# heater-control.net
KiCad netlist of a schematic drawn in Altium Designer
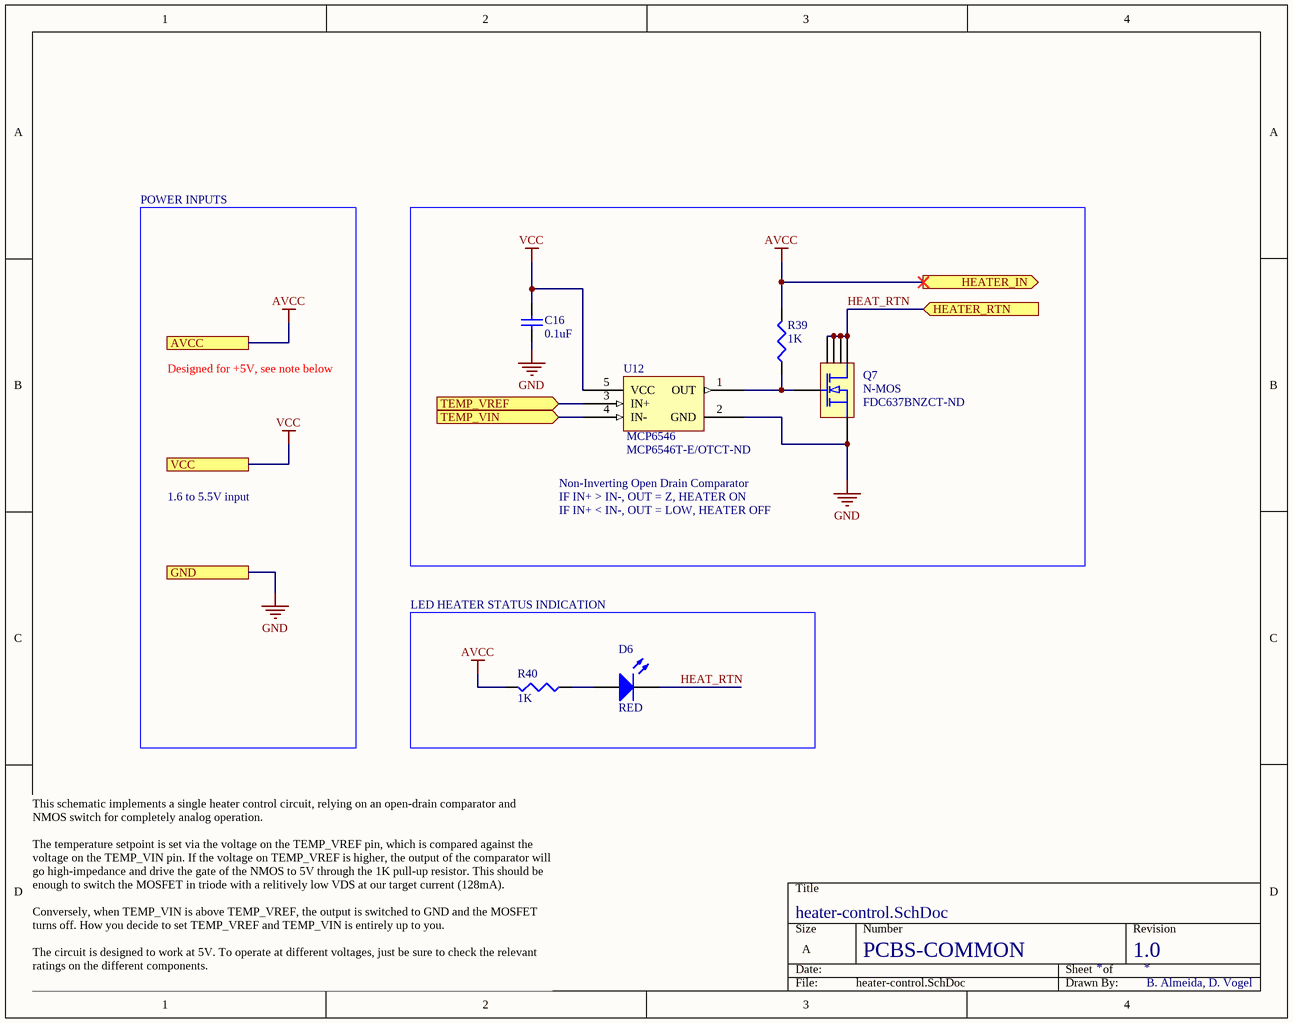
[diagram p0: heater-control.SchDoc]

(export (version "E")
  (design (tool "Eeschema 10.0.6"))
  (components
    (comp (ref "C16")
      (value "0.1uF")
      (footprint "1608[0603]")
      (description "Capacitor (Semiconductor SIM Model)")
      (fields (field (name "Comment") "100pF") (field (name "PUBLISHER") "Altium Limited"))
      (libsource (lib "Miscellaneous Devices") (part "Cap Semi"))
    )
    (comp (ref "D6")
      (value "RED")
      (footprint "0603-LED")
      (description "Typical RED, GREEN, YELLOW, AMBER GaAs LED")
      (fields (field (name "PUBLISHER") "Altium Limited"))
      (libsource (lib "Miscellaneous Devices") (part "LED2"))
    )
    (comp (ref "Q7")
      (value "N-MOS")
      (footprint "SOT95P280X145-6N")
      (description "N-MOS, low gate ON voltage")
      (fields (field (name "SUPPLIER PART NUMBER") "FDC637BNZCT-ND"))
      (libsource (lib "PAY") (part "FDC637BNZCT-ND"))
    )
    (comp (ref "R39")
      (value "1K")
      (footprint "J1-0603")
      (description "Resistor")
      (fields (field (name "PUBLISHER") "Altium Limited"))
      (libsource (lib "Miscellaneous Devices") (part "Res3"))
    )
    (comp (ref "R40")
      (value "1K")
      (footprint "J1-0603")
      (description "Resistor")
      (fields (field (name "PUBLISHER") "Altium Limited"))
      (libsource (lib "Miscellaneous Devices") (part "Res3"))
    )
    (comp (ref "U12")
      (value "MCP6546")
      (footprint "SOT-23-5_95P290X160-5N")
      (description "Open-drain output sub-microamp comparator.")
      (fields (field (name "SUPPLIER PART NUMBER 1") "MCP6546T-E/OTCT-ND"))
      (libsource (lib "PAY") (part "MCP6546"))
    )
  )
  (nets
    (net (code "1") (name "/HEAT_RTN") (class "Default")
      (node (ref "D6") (pin "2") (pinfunction "K_2") (pintype "passive"))
      (node (ref "Q7") (pin "1") (pinfunction "D_1") (pintype "passive"))
      (node (ref "Q7") (pin "2") (pinfunction "D_2") (pintype "passive"))
      (node (ref "Q7") (pin "5") (pinfunction "D_5") (pintype "passive"))
      (node (ref "Q7") (pin "6") (pinfunction "D_6") (pintype "passive"))
    )
    (net (code "2") (name "/TEMP_VIN") (class "Default")
      (node (ref "U12") (pin "4") (pinfunction "IN-_4") (pintype "input"))
    )
    (net (code "3") (name "/TEMP_VREF") (class "Default")
      (node (ref "U12") (pin "3") (pinfunction "IN+_3") (pintype "input"))
    )
    (net (code "4") (name "AVCC") (class "Default")
      (node (ref "R39") (pin "2") (pinfunction "2_2") (pintype "passive"))
      (node (ref "R40") (pin "2") (pinfunction "2_2") (pintype "passive"))
    )
    (net (code "5") (name "GND") (class "Default")
      (node (ref "C16") (pin "1") (pinfunction "1_1") (pintype "passive"))
      (node (ref "Q7") (pin "4") (pinfunction "S_4") (pintype "passive"))
      (node (ref "U12") (pin "2") (pinfunction "GND_2") (pintype "power_in"))
    )
    (net (code "6") (name "Net-(D6-A)") (class "Default")
      (node (ref "D6") (pin "1") (pinfunction "A_1") (pintype "passive"))
      (node (ref "R40") (pin "1") (pinfunction "1_1") (pintype "passive"))
    )
    (net (code "7") (name "Net-(Q7-G)") (class "Default")
      (node (ref "Q7") (pin "3") (pinfunction "G_3") (pintype "passive"))
      (node (ref "R39") (pin "1") (pinfunction "1_1") (pintype "passive"))
      (node (ref "U12") (pin "1") (pinfunction "OUT_1") (pintype "output"))
    )
    (net (code "8") (name "VCC") (class "Default")
      (node (ref "C16") (pin "2") (pinfunction "2_2") (pintype "passive"))
      (node (ref "U12") (pin "5") (pinfunction "VCC_5") (pintype "power_in"))
    )
  )
)
